# tweezer.net
KiCad netlist of a schematic drawn in EAGLE
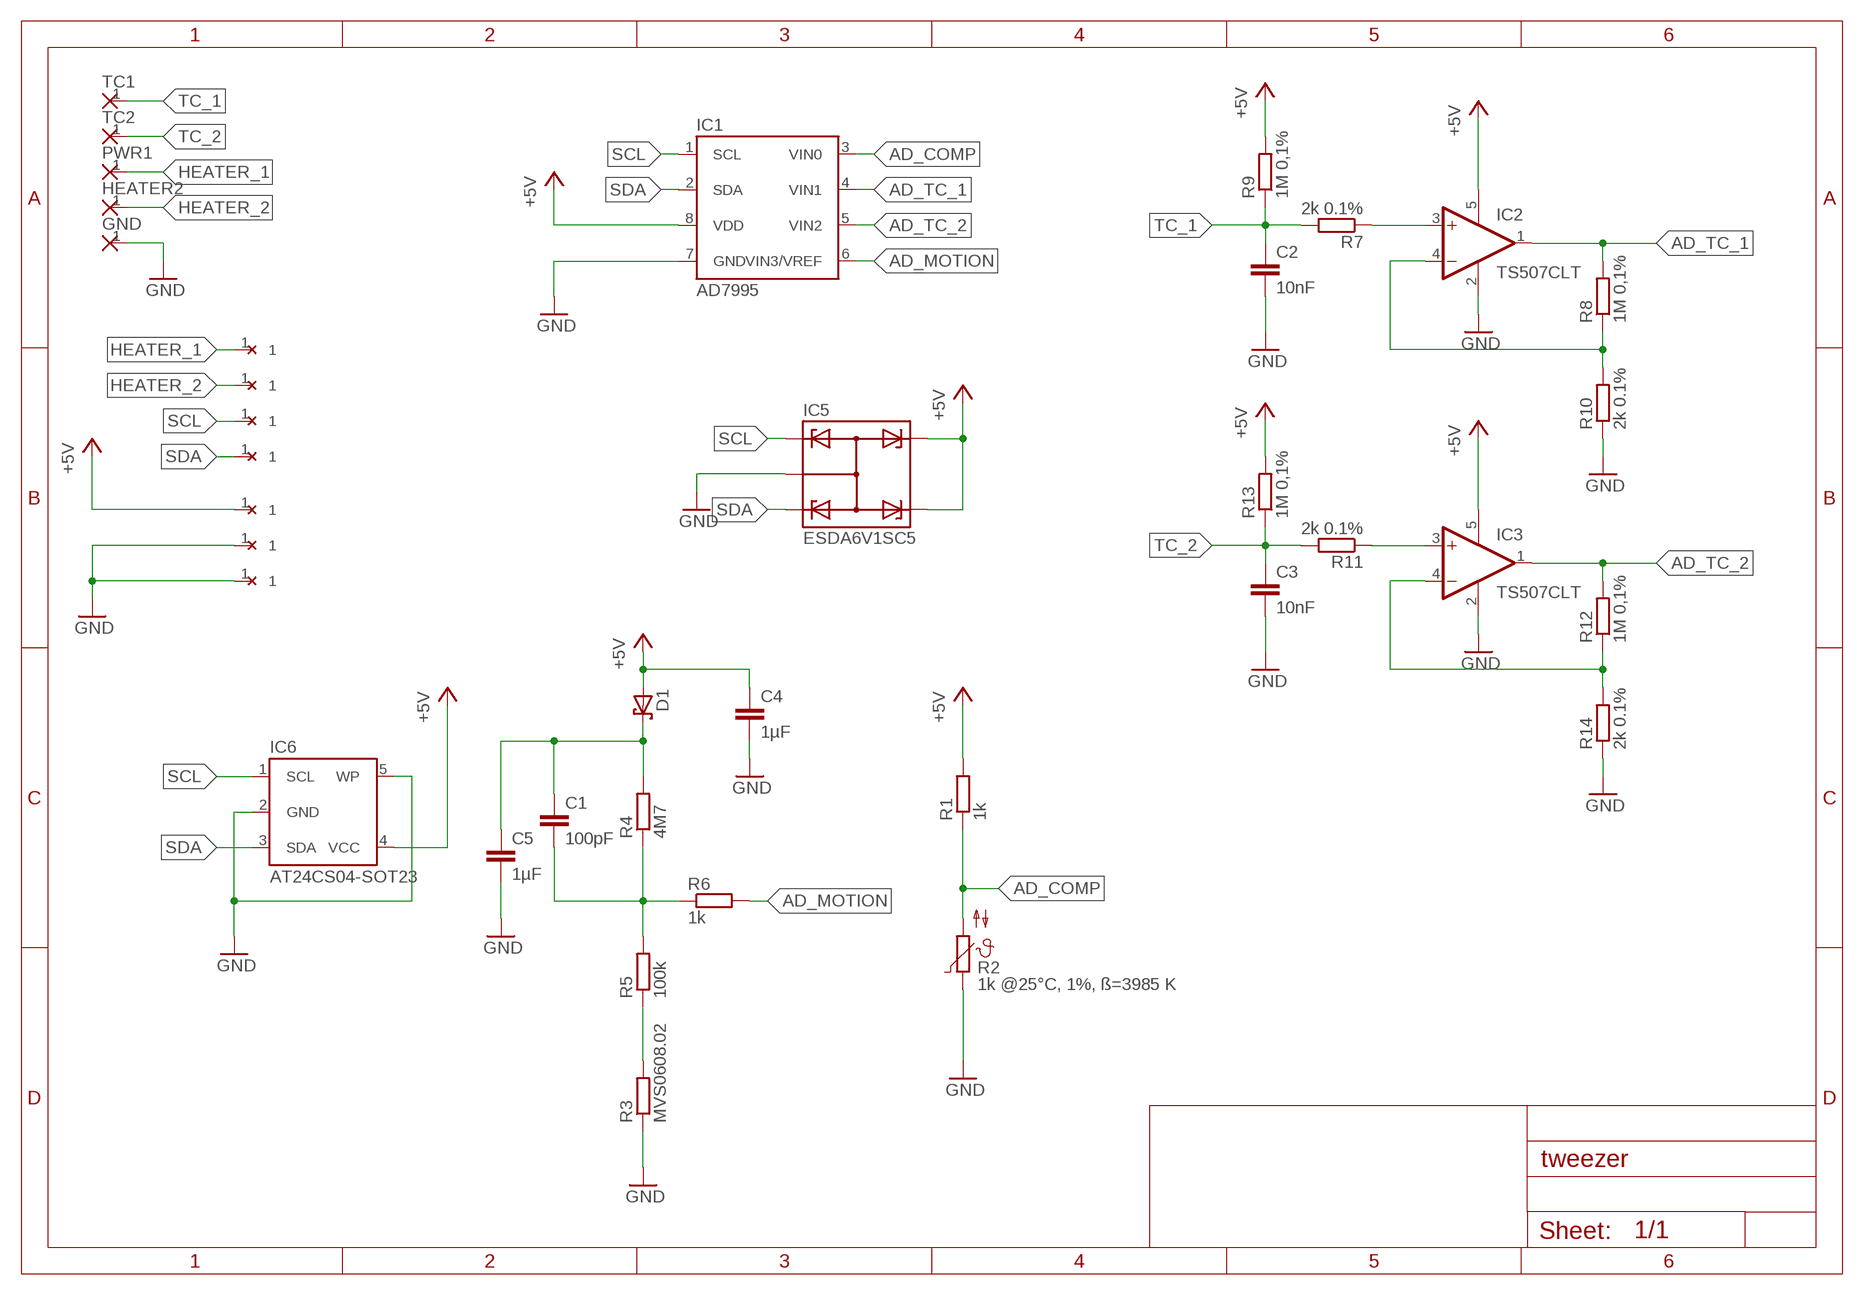
[diagram p0: schematic, sheet 1]

(export (version "E")
  (design (tool "Eeschema 10.0.6"))
  (components
    (comp (ref "21")
      (value "WIREPAD")
      (footprint "eagle-import:WIREPAD")
      (libsource (lib "eagle-import") (part "WIREPAD"))
    )
    (comp (ref "C1")
      (value "100pF")
      (footprint "eagle-import:C0603")
      (libsource (lib "eagle-import") (part "C-EU0603"))
    )
    (comp (ref "C2")
      (value "10nF")
      (footprint "eagle-import:C0603")
      (libsource (lib "eagle-import") (part "C-EU0603"))
    )
    (comp (ref "C3")
      (value "10nF")
      (footprint "eagle-import:C0603")
      (libsource (lib "eagle-import") (part "C-EU0603"))
    )
    (comp (ref "C4")
      (value "1µF")
      (footprint "eagle-import:C0603")
      (libsource (lib "eagle-import") (part "C-EU0603"))
    )
    (comp (ref "C5")
      (value "1µF")
      (footprint "eagle-import:C0603")
      (libsource (lib "eagle-import") (part "C-EU0603"))
    )
    (comp (ref "D1")
      (value "BAT54H")
      (footprint "eagle-import:SOD123-F")
      (libsource (lib "eagle-import") (part "BAT54H"))
    )
    (comp (ref "GND")
      (value "1,6/0,8")
      (footprint "eagle-import:1,6_0,8")
      (libsource (lib "eagle-import") (part "1,6/0,8"))
    )
    (comp (ref "HEATER2")
      (value "1,6/0,8")
      (footprint "eagle-import:1,6_0,8")
      (libsource (lib "eagle-import") (part "1,6/0,8"))
    )
    (comp (ref "IC1")
      (value "AD7995")
      (footprint "eagle-import:SOT23-8")
      (libsource (lib "eagle-import") (part "AD7995"))
    )
    (comp (ref "IC2")
      (value "TS507CLT")
      (footprint "eagle-import:SOT23-5L")
      (libsource (lib "eagle-import") (part "TS507CLT"))
    )
    (comp (ref "IC3")
      (value "TS507CLT")
      (footprint "eagle-import:SOT23-5L")
      (libsource (lib "eagle-import") (part "TS507CLT"))
    )
    (comp (ref "IC5")
      (value "ESDA6V1SC5")
      (footprint "eagle-import:SOT23-5L")
      (libsource (lib "eagle-import") (part "ESDA6V1SC5"))
    )
    (comp (ref "IC6")
      (value "AT24CS04-SOT23")
      (footprint "eagle-import:SOT23-5L")
      (libsource (lib "eagle-import") (part "AT24CS04-SOT23"))
    )
    (comp (ref "PWR1")
      (value "1,6/0,8")
      (footprint "eagle-import:1,6_0,8")
      (libsource (lib "eagle-import") (part "1,6/0,8"))
    )
    (comp (ref "R1")
      (value "1k")
      (footprint "eagle-import:R0603")
      (libsource (lib "eagle-import") (part "R-EU0603"))
    )
    (comp (ref "R2")
      (value "1k @25°C, 1%, ß=3985 K")
      (footprint "eagle-import:R0603")
      (libsource (lib "eagle-import") (part "NTC0603"))
    )
    (comp (ref "R3")
      (value "MVS0608.02")
      (footprint "eagle-import:VIBRA-SNS")
      (libsource (lib "eagle-import") (part "MVS0608.02"))
    )
    (comp (ref "R4")
      (value "4M7")
      (footprint "eagle-import:R0603")
      (libsource (lib "eagle-import") (part "R-EU0603"))
    )
    (comp (ref "R5")
      (value "100k")
      (footprint "eagle-import:R0603")
      (libsource (lib "eagle-import") (part "R-EU0603"))
    )
    (comp (ref "R6")
      (value "1k")
      (footprint "eagle-import:R0603")
      (libsource (lib "eagle-import") (part "R-EU0603"))
    )
    (comp (ref "R7")
      (value "2k 0.1%")
      (footprint "eagle-import:R0603")
      (libsource (lib "eagle-import") (part "R-EU0603"))
    )
    (comp (ref "R8")
      (value "1M 0,1%")
      (footprint "eagle-import:R0603")
      (libsource (lib "eagle-import") (part "R-EU0603"))
    )
    (comp (ref "R9")
      (value "1M 0,1%")
      (footprint "eagle-import:R0603")
      (libsource (lib "eagle-import") (part "R-EU0603"))
    )
    (comp (ref "R10")
      (value "2k 0.1%")
      (footprint "eagle-import:R0603")
      (libsource (lib "eagle-import") (part "R-EU0603"))
    )
    (comp (ref "R11")
      (value "2k 0.1%")
      (footprint "eagle-import:R0603")
      (libsource (lib "eagle-import") (part "R-EU0603"))
    )
    (comp (ref "R12")
      (value "1M 0,1%")
      (footprint "eagle-import:R0603")
      (libsource (lib "eagle-import") (part "R-EU0603"))
    )
    (comp (ref "R13")
      (value "1M 0,1%")
      (footprint "eagle-import:R0603")
      (libsource (lib "eagle-import") (part "R-EU0603"))
    )
    (comp (ref "R14")
      (value "2k 0.1%")
      (footprint "eagle-import:R0603")
      (libsource (lib "eagle-import") (part "R-EU0603"))
    )
    (comp (ref "TC1")
      (value "1,6/0,8")
      (footprint "eagle-import:1,6_0,8")
      (libsource (lib "eagle-import") (part "1,6/0,8"))
    )
    (comp (ref "TC2")
      (value "1,6/0,8")
      (footprint "eagle-import:1,6_0,8")
      (libsource (lib "eagle-import") (part "1,6/0,8"))
    )
    (comp (ref "U$1")
      (value "WIREPAD")
      (footprint "eagle-import:WIREPAD")
      (libsource (lib "eagle-import") (part "WIREPAD"))
    )
    (comp (ref "U$7")
      (value "WIREPAD")
      (footprint "eagle-import:WIREPAD")
      (libsource (lib "eagle-import") (part "WIREPAD"))
    )
    (comp (ref "U$9")
      (value "WIREPAD")
      (footprint "eagle-import:WIREPAD")
      (libsource (lib "eagle-import") (part "WIREPAD"))
    )
    (comp (ref "U$10")
      (value "WIREPAD")
      (footprint "eagle-import:WIREPAD")
      (libsource (lib "eagle-import") (part "WIREPAD"))
    )
    (comp (ref "U$11")
      (value "WIREPAD")
      (footprint "eagle-import:WIREPAD")
      (libsource (lib "eagle-import") (part "WIREPAD"))
    )
    (comp (ref "ß")
      (value "WIREPAD")
      (footprint "eagle-import:WIREPAD")
      (libsource (lib "eagle-import") (part "WIREPAD"))
    )
  )
  (nets
    (net (code "1") (name "+5V") (class "Default")
      (node (ref "C4") (pin "1") (pinfunction "1_1") (pintype "passive"))
      (node (ref "D1") (pin "2") (pinfunction "A_2") (pintype "passive"))
      (node (ref "IC1") (pin "8") (pinfunction "VDD_8") (pintype "bidirectional"))
      (node (ref "IC2") (pin "5") (pinfunction "V+_5") (pintype "power_in"))
      (node (ref "IC3") (pin "5") (pinfunction "V+_5") (pintype "power_in"))
      (node (ref "IC5") (pin "4") (pinfunction "4_4") (pintype "passive"))
      (node (ref "IC5") (pin "5") (pinfunction "5_5") (pintype "passive"))
      (node (ref "IC6") (pin "4") (pinfunction "VCC_4") (pintype "bidirectional"))
      (node (ref "R1") (pin "2") (pinfunction "2_2") (pintype "passive"))
      (node (ref "R13") (pin "2") (pinfunction "2_2") (pintype "passive"))
      (node (ref "R9") (pin "2") (pinfunction "2_2") (pintype "passive"))
      (node (ref "U$10") (pin "1") (pinfunction "1_1") (pintype "passive"))
    )
    (net (code "2") (name "AD_COMP") (class "Default")
      (node (ref "IC1") (pin "3") (pinfunction "VIN0_3") (pintype "bidirectional"))
      (node (ref "R1") (pin "1") (pinfunction "1_1") (pintype "passive"))
      (node (ref "R2") (pin "2") (pinfunction "2_2") (pintype "passive"))
    )
    (net (code "3") (name "AD_MOTION") (class "Default")
      (node (ref "IC1") (pin "6") (pinfunction "VIN3/VREF_6") (pintype "bidirectional"))
      (node (ref "R6") (pin "2") (pinfunction "2_2") (pintype "passive"))
    )
    (net (code "4") (name "AD_TC_1") (class "Default")
      (node (ref "IC1") (pin "4") (pinfunction "VIN1_4") (pintype "bidirectional"))
      (node (ref "IC2") (pin "1") (pinfunction "OUT_1") (pintype "output"))
      (node (ref "R8") (pin "2") (pinfunction "2_2") (pintype "passive"))
    )
    (net (code "5") (name "AD_TC_2") (class "Default")
      (node (ref "IC1") (pin "5") (pinfunction "VIN2_5") (pintype "bidirectional"))
      (node (ref "IC3") (pin "1") (pinfunction "OUT_1") (pintype "output"))
      (node (ref "R12") (pin "2") (pinfunction "2_2") (pintype "passive"))
    )
    (net (code "6") (name "GND") (class "Default")
      (node (ref "C2") (pin "2") (pinfunction "2_2") (pintype "passive"))
      (node (ref "C3") (pin "2") (pinfunction "2_2") (pintype "passive"))
      (node (ref "C4") (pin "2") (pinfunction "2_2") (pintype "passive"))
      (node (ref "C5") (pin "2") (pinfunction "2_2") (pintype "passive"))
      (node (ref "GND") (pin "1") (pinfunction "P_1") (pintype "passive"))
      (node (ref "IC1") (pin "7") (pinfunction "GND_7") (pintype "bidirectional"))
      (node (ref "IC2") (pin "2") (pinfunction "V-_2") (pintype "power_in"))
      (node (ref "IC3") (pin "2") (pinfunction "V-_2") (pintype "power_in"))
      (node (ref "IC5") (pin "2") (pinfunction "2_2") (pintype "passive"))
      (node (ref "IC6") (pin "2") (pinfunction "GND_2") (pintype "bidirectional"))
      (node (ref "IC6") (pin "5") (pinfunction "WP_5") (pintype "bidirectional"))
      (node (ref "R10") (pin "1") (pinfunction "1_1") (pintype "passive"))
      (node (ref "R14") (pin "1") (pinfunction "1_1") (pintype "passive"))
      (node (ref "R2") (pin "1") (pinfunction "1_1") (pintype "passive"))
      (node (ref "R3") (pin "P$1") (pinfunction "1_P$1") (pintype "passive"))
      (node (ref "U$1") (pin "1") (pinfunction "1_1") (pintype "passive"))
      (node (ref "U$11") (pin "1") (pinfunction "1_1") (pintype "passive"))
    )
    (net (code "7") (name "HEATER_1") (class "Default")
      (node (ref "PWR1") (pin "1") (pinfunction "P_1") (pintype "passive"))
      (node (ref "ß") (pin "1") (pinfunction "1_1") (pintype "passive"))
    )
    (net (code "8") (name "HEATER_2") (class "Default")
      (node (ref "HEATER2") (pin "1") (pinfunction "P_1") (pintype "passive"))
      (node (ref "U$7") (pin "1") (pinfunction "1_1") (pintype "passive"))
    )
    (net (code "9") (name "Net-(C1-Pad2)") (class "Default")
      (node (ref "C1") (pin "2") (pinfunction "2_2") (pintype "passive"))
      (node (ref "R4") (pin "1") (pinfunction "1_1") (pintype "passive"))
      (node (ref "R5") (pin "2") (pinfunction "2_2") (pintype "passive"))
      (node (ref "R6") (pin "1") (pinfunction "1_1") (pintype "passive"))
    )
    (net (code "10") (name "Net-(D1-C)") (class "Default")
      (node (ref "C1") (pin "1") (pinfunction "1_1") (pintype "passive"))
      (node (ref "C5") (pin "1") (pinfunction "1_1") (pintype "passive"))
      (node (ref "D1") (pin "1") (pinfunction "C_1") (pintype "passive"))
      (node (ref "R4") (pin "2") (pinfunction "2_2") (pintype "passive"))
    )
    (net (code "11") (name "Net-(IC2-+IN)") (class "Default")
      (node (ref "IC2") (pin "3") (pinfunction "+IN_3") (pintype "input"))
      (node (ref "R7") (pin "1") (pinfunction "1_1") (pintype "passive"))
    )
    (net (code "12") (name "Net-(IC2--IN)") (class "Default")
      (node (ref "IC2") (pin "4") (pinfunction "-IN_4") (pintype "input"))
      (node (ref "R10") (pin "2") (pinfunction "2_2") (pintype "passive"))
      (node (ref "R8") (pin "1") (pinfunction "1_1") (pintype "passive"))
    )
    (net (code "13") (name "Net-(IC3-+IN)") (class "Default")
      (node (ref "IC3") (pin "3") (pinfunction "+IN_3") (pintype "input"))
      (node (ref "R11") (pin "1") (pinfunction "1_1") (pintype "passive"))
    )
    (net (code "14") (name "Net-(IC3--IN)") (class "Default")
      (node (ref "IC3") (pin "4") (pinfunction "-IN_4") (pintype "input"))
      (node (ref "R12") (pin "1") (pinfunction "1_1") (pintype "passive"))
      (node (ref "R14") (pin "2") (pinfunction "2_2") (pintype "passive"))
    )
    (net (code "15") (name "Net-(R3-2)") (class "Default")
      (node (ref "R3") (pin "P$2") (pinfunction "2_P$2") (pintype "passive"))
      (node (ref "R5") (pin "1") (pinfunction "1_1") (pintype "passive"))
    )
    (net (code "16") (name "SCL") (class "Default")
      (node (ref "21") (pin "1") (pinfunction "1_1") (pintype "passive"))
      (node (ref "IC1") (pin "1") (pinfunction "SCL_1") (pintype "bidirectional"))
      (node (ref "IC5") (pin "1") (pinfunction "1_1") (pintype "passive"))
      (node (ref "IC6") (pin "1") (pinfunction "SCL_1") (pintype "bidirectional"))
    )
    (net (code "17") (name "SDA") (class "Default")
      (node (ref "IC1") (pin "2") (pinfunction "SDA_2") (pintype "bidirectional"))
      (node (ref "IC5") (pin "3") (pinfunction "3_3") (pintype "passive"))
      (node (ref "IC6") (pin "3") (pinfunction "SDA_3") (pintype "bidirectional"))
      (node (ref "U$9") (pin "1") (pinfunction "1_1") (pintype "passive"))
    )
    (net (code "18") (name "TC_1") (class "Default")
      (node (ref "C2") (pin "1") (pinfunction "1_1") (pintype "passive"))
      (node (ref "R7") (pin "2") (pinfunction "2_2") (pintype "passive"))
      (node (ref "R9") (pin "1") (pinfunction "1_1") (pintype "passive"))
      (node (ref "TC1") (pin "1") (pinfunction "P_1") (pintype "passive"))
    )
    (net (code "19") (name "TC_2") (class "Default")
      (node (ref "C3") (pin "1") (pinfunction "1_1") (pintype "passive"))
      (node (ref "R11") (pin "2") (pinfunction "2_2") (pintype "passive"))
      (node (ref "R13") (pin "1") (pinfunction "1_1") (pintype "passive"))
      (node (ref "TC2") (pin "1") (pinfunction "P_1") (pintype "passive"))
    )
  )
)
